# pqfb100-breakout.net
KiCad netlist of a schematic drawn in EAGLE
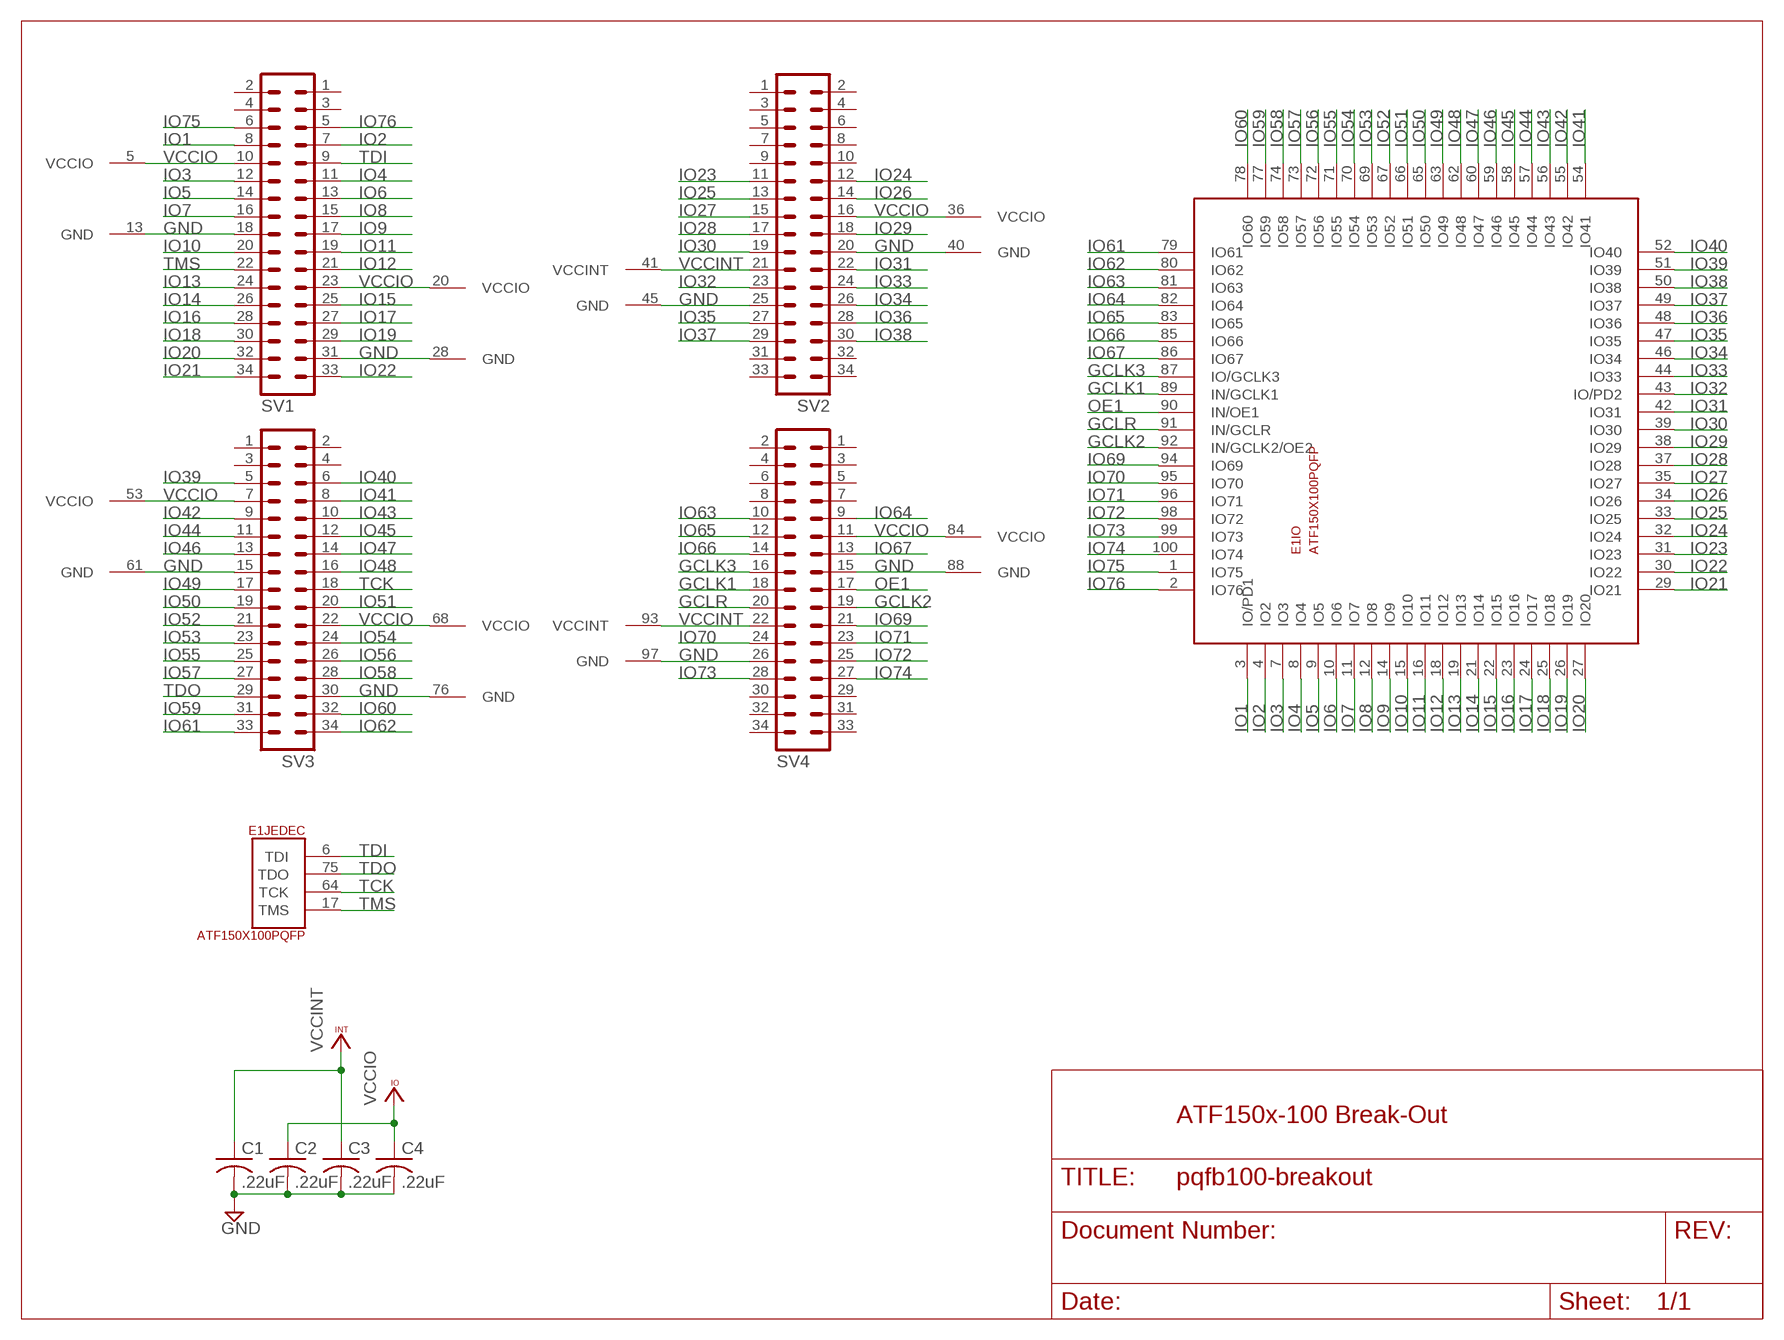
[diagram p0: schematic, sheet 1]

(export (version "E")
  (design (tool "Eeschema 10.0.6"))
  (components
    (comp (ref "C1")
      (value ".22uF")
      (footprint "eagle-import:C063-025X075")
      (libsource (lib "eagle-import") (part "C-US"))
    )
    (comp (ref "C2")
      (value ".22uF")
      (footprint "eagle-import:C063-025X075")
      (libsource (lib "eagle-import") (part "C-US"))
    )
    (comp (ref "C3")
      (value ".22uF")
      (footprint "eagle-import:C063-025X075")
      (libsource (lib "eagle-import") (part "C-US"))
    )
    (comp (ref "C4")
      (value ".22uF")
      (footprint "eagle-import:C063-025X075")
      (libsource (lib "eagle-import") (part "C-US"))
    )
    (comp (ref "E1")
      (value "ATF150X100PQFP")
      (footprint "eagle-import:PQFP-100")
      (libsource (lib "eagle-import") (part "ATF150X100PQFP"))
    )
    (comp (ref "SV1")
      (value "MA17-2")
      (footprint "eagle-import:MA17-2")
      (libsource (lib "eagle-import") (part "MA17-2"))
    )
    (comp (ref "SV2")
      (value "MA17-2")
      (footprint "eagle-import:MA17-2")
      (libsource (lib "eagle-import") (part "MA17-2"))
    )
    (comp (ref "SV3")
      (value "MA17-2")
      (footprint "eagle-import:MA17-2")
      (libsource (lib "eagle-import") (part "MA17-2"))
    )
    (comp (ref "SV4")
      (value "MA17-2")
      (footprint "eagle-import:MA17-2")
      (libsource (lib "eagle-import") (part "MA17-2"))
    )
  )
  (nets
    (net (code "1") (name "/GCLK1") (class "Default")
      (node (ref "E1") (pin "89") (pinfunction "IN/GCLK1_89") (pintype "input"))
      (node (ref "SV4") (pin "18") (pinfunction "18_18") (pintype "passive"))
    )
    (net (code "2") (name "/GCLK2") (class "Default")
      (node (ref "E1") (pin "92") (pinfunction "IN/GCLK2/OE2_92") (pintype "input"))
      (node (ref "SV4") (pin "19") (pinfunction "19_19") (pintype "passive"))
    )
    (net (code "3") (name "/GCLK3") (class "Default")
      (node (ref "E1") (pin "87") (pinfunction "IO/GCLK3_87") (pintype "bidirectional"))
      (node (ref "SV4") (pin "16") (pinfunction "16_16") (pintype "passive"))
    )
    (net (code "4") (name "/GCLR") (class "Default")
      (node (ref "E1") (pin "91") (pinfunction "IN/GCLR_91") (pintype "input"))
      (node (ref "SV4") (pin "20") (pinfunction "20_20") (pintype "passive"))
    )
    (net (code "5") (name "/IO1") (class "Default")
      (node (ref "E1") (pin "3") (pinfunction "IO/PD1_3") (pintype "bidirectional"))
      (node (ref "SV1") (pin "8") (pinfunction "8_8") (pintype "passive"))
    )
    (net (code "6") (name "/IO2") (class "Default")
      (node (ref "E1") (pin "4") (pinfunction "IO2_4") (pintype "bidirectional"))
      (node (ref "SV1") (pin "7") (pinfunction "7_7") (pintype "passive"))
    )
    (net (code "7") (name "/IO3") (class "Default")
      (node (ref "E1") (pin "7") (pinfunction "IO3_7") (pintype "bidirectional"))
      (node (ref "SV1") (pin "12") (pinfunction "12_12") (pintype "passive"))
    )
    (net (code "8") (name "/IO4") (class "Default")
      (node (ref "E1") (pin "8") (pinfunction "IO4_8") (pintype "bidirectional"))
      (node (ref "SV1") (pin "11") (pinfunction "11_11") (pintype "passive"))
    )
    (net (code "9") (name "/IO5") (class "Default")
      (node (ref "E1") (pin "9") (pinfunction "IO5_9") (pintype "bidirectional"))
      (node (ref "SV1") (pin "14") (pinfunction "14_14") (pintype "passive"))
    )
    (net (code "10") (name "/IO6") (class "Default")
      (node (ref "E1") (pin "10") (pinfunction "IO6_10") (pintype "bidirectional"))
      (node (ref "SV1") (pin "13") (pinfunction "13_13") (pintype "passive"))
    )
    (net (code "11") (name "/IO7") (class "Default")
      (node (ref "E1") (pin "11") (pinfunction "IO7_11") (pintype "bidirectional"))
      (node (ref "SV1") (pin "16") (pinfunction "16_16") (pintype "passive"))
    )
    (net (code "12") (name "/IO8") (class "Default")
      (node (ref "E1") (pin "12") (pinfunction "IO8_12") (pintype "bidirectional"))
      (node (ref "SV1") (pin "15") (pinfunction "15_15") (pintype "passive"))
    )
    (net (code "13") (name "/IO9") (class "Default")
      (node (ref "E1") (pin "14") (pinfunction "IO9_14") (pintype "bidirectional"))
      (node (ref "SV1") (pin "17") (pinfunction "17_17") (pintype "passive"))
    )
    (net (code "14") (name "/IO10") (class "Default")
      (node (ref "E1") (pin "15") (pinfunction "IO10_15") (pintype "bidirectional"))
      (node (ref "SV1") (pin "20") (pinfunction "20_20") (pintype "passive"))
    )
    (net (code "15") (name "/IO11") (class "Default")
      (node (ref "E1") (pin "16") (pinfunction "IO11_16") (pintype "bidirectional"))
      (node (ref "SV1") (pin "19") (pinfunction "19_19") (pintype "passive"))
    )
    (net (code "16") (name "/IO12") (class "Default")
      (node (ref "E1") (pin "18") (pinfunction "IO12_18") (pintype "bidirectional"))
      (node (ref "SV1") (pin "21") (pinfunction "21_21") (pintype "passive"))
    )
    (net (code "17") (name "/IO13") (class "Default")
      (node (ref "E1") (pin "19") (pinfunction "IO13_19") (pintype "bidirectional"))
      (node (ref "SV1") (pin "24") (pinfunction "24_24") (pintype "passive"))
    )
    (net (code "18") (name "/IO14") (class "Default")
      (node (ref "E1") (pin "21") (pinfunction "IO14_21") (pintype "bidirectional"))
      (node (ref "SV1") (pin "26") (pinfunction "26_26") (pintype "passive"))
    )
    (net (code "19") (name "/IO15") (class "Default")
      (node (ref "E1") (pin "22") (pinfunction "IO15_22") (pintype "bidirectional"))
      (node (ref "SV1") (pin "25") (pinfunction "25_25") (pintype "passive"))
    )
    (net (code "20") (name "/IO16") (class "Default")
      (node (ref "E1") (pin "23") (pinfunction "IO16_23") (pintype "bidirectional"))
      (node (ref "SV1") (pin "28") (pinfunction "28_28") (pintype "passive"))
    )
    (net (code "21") (name "/IO17") (class "Default")
      (node (ref "E1") (pin "24") (pinfunction "IO17_24") (pintype "bidirectional"))
      (node (ref "SV1") (pin "27") (pinfunction "27_27") (pintype "passive"))
    )
    (net (code "22") (name "/IO18") (class "Default")
      (node (ref "E1") (pin "25") (pinfunction "IO18_25") (pintype "bidirectional"))
      (node (ref "SV1") (pin "30") (pinfunction "30_30") (pintype "passive"))
    )
    (net (code "23") (name "/IO19") (class "Default")
      (node (ref "E1") (pin "26") (pinfunction "IO19_26") (pintype "bidirectional"))
      (node (ref "SV1") (pin "29") (pinfunction "29_29") (pintype "passive"))
    )
    (net (code "24") (name "/IO20") (class "Default")
      (node (ref "E1") (pin "27") (pinfunction "IO20_27") (pintype "bidirectional"))
      (node (ref "SV1") (pin "32") (pinfunction "32_32") (pintype "passive"))
    )
    (net (code "25") (name "/IO21") (class "Default")
      (node (ref "E1") (pin "29") (pinfunction "IO21_29") (pintype "bidirectional"))
      (node (ref "SV1") (pin "34") (pinfunction "34_34") (pintype "passive"))
    )
    (net (code "26") (name "/IO22") (class "Default")
      (node (ref "E1") (pin "30") (pinfunction "IO22_30") (pintype "bidirectional"))
      (node (ref "SV1") (pin "33") (pinfunction "33_33") (pintype "passive"))
    )
    (net (code "27") (name "/IO23") (class "Default")
      (node (ref "E1") (pin "31") (pinfunction "IO23_31") (pintype "bidirectional"))
      (node (ref "SV2") (pin "11") (pinfunction "11_11") (pintype "passive"))
    )
    (net (code "28") (name "/IO24") (class "Default")
      (node (ref "E1") (pin "32") (pinfunction "IO24_32") (pintype "bidirectional"))
      (node (ref "SV2") (pin "12") (pinfunction "12_12") (pintype "passive"))
    )
    (net (code "29") (name "/IO25") (class "Default")
      (node (ref "E1") (pin "33") (pinfunction "IO25_33") (pintype "bidirectional"))
      (node (ref "SV2") (pin "13") (pinfunction "13_13") (pintype "passive"))
    )
    (net (code "30") (name "/IO26") (class "Default")
      (node (ref "E1") (pin "34") (pinfunction "IO26_34") (pintype "bidirectional"))
      (node (ref "SV2") (pin "14") (pinfunction "14_14") (pintype "passive"))
    )
    (net (code "31") (name "/IO27") (class "Default")
      (node (ref "E1") (pin "35") (pinfunction "IO27_35") (pintype "bidirectional"))
      (node (ref "SV2") (pin "15") (pinfunction "15_15") (pintype "passive"))
    )
    (net (code "32") (name "/IO28") (class "Default")
      (node (ref "E1") (pin "37") (pinfunction "IO28_37") (pintype "bidirectional"))
      (node (ref "SV2") (pin "17") (pinfunction "17_17") (pintype "passive"))
    )
    (net (code "33") (name "/IO29") (class "Default")
      (node (ref "E1") (pin "38") (pinfunction "IO29_38") (pintype "bidirectional"))
      (node (ref "SV2") (pin "18") (pinfunction "18_18") (pintype "passive"))
    )
    (net (code "34") (name "/IO30") (class "Default")
      (node (ref "E1") (pin "39") (pinfunction "IO30_39") (pintype "bidirectional"))
      (node (ref "SV2") (pin "19") (pinfunction "19_19") (pintype "passive"))
    )
    (net (code "35") (name "/IO31") (class "Default")
      (node (ref "E1") (pin "42") (pinfunction "IO31_42") (pintype "bidirectional"))
      (node (ref "SV2") (pin "22") (pinfunction "22_22") (pintype "passive"))
    )
    (net (code "36") (name "/IO32") (class "Default")
      (node (ref "E1") (pin "43") (pinfunction "IO/PD2_43") (pintype "bidirectional"))
      (node (ref "SV2") (pin "23") (pinfunction "23_23") (pintype "passive"))
    )
    (net (code "37") (name "/IO33") (class "Default")
      (node (ref "E1") (pin "44") (pinfunction "IO33_44") (pintype "bidirectional"))
      (node (ref "SV2") (pin "24") (pinfunction "24_24") (pintype "passive"))
    )
    (net (code "38") (name "/IO34") (class "Default")
      (node (ref "E1") (pin "46") (pinfunction "IO34_46") (pintype "bidirectional"))
      (node (ref "SV2") (pin "26") (pinfunction "26_26") (pintype "passive"))
    )
    (net (code "39") (name "/IO35") (class "Default")
      (node (ref "E1") (pin "47") (pinfunction "IO35_47") (pintype "bidirectional"))
      (node (ref "SV2") (pin "27") (pinfunction "27_27") (pintype "passive"))
    )
    (net (code "40") (name "/IO36") (class "Default")
      (node (ref "E1") (pin "48") (pinfunction "IO36_48") (pintype "bidirectional"))
      (node (ref "SV2") (pin "28") (pinfunction "28_28") (pintype "passive"))
    )
    (net (code "41") (name "/IO37") (class "Default")
      (node (ref "E1") (pin "49") (pinfunction "IO37_49") (pintype "bidirectional"))
      (node (ref "SV2") (pin "29") (pinfunction "29_29") (pintype "passive"))
    )
    (net (code "42") (name "/IO38") (class "Default")
      (node (ref "E1") (pin "50") (pinfunction "IO38_50") (pintype "bidirectional"))
      (node (ref "SV2") (pin "30") (pinfunction "30_30") (pintype "passive"))
    )
    (net (code "43") (name "/IO39") (class "Default")
      (node (ref "E1") (pin "51") (pinfunction "IO39_51") (pintype "bidirectional"))
      (node (ref "SV3") (pin "5") (pinfunction "5_5") (pintype "passive"))
    )
    (net (code "44") (name "/IO40") (class "Default")
      (node (ref "E1") (pin "52") (pinfunction "IO40_52") (pintype "bidirectional"))
      (node (ref "SV3") (pin "6") (pinfunction "6_6") (pintype "passive"))
    )
    (net (code "45") (name "/IO41") (class "Default")
      (node (ref "E1") (pin "54") (pinfunction "IO41_54") (pintype "bidirectional"))
      (node (ref "SV3") (pin "8") (pinfunction "8_8") (pintype "passive"))
    )
    (net (code "46") (name "/IO42") (class "Default")
      (node (ref "E1") (pin "55") (pinfunction "IO42_55") (pintype "bidirectional"))
      (node (ref "SV3") (pin "9") (pinfunction "9_9") (pintype "passive"))
    )
    (net (code "47") (name "/IO43") (class "Default")
      (node (ref "E1") (pin "56") (pinfunction "IO43_56") (pintype "bidirectional"))
      (node (ref "SV3") (pin "10") (pinfunction "10_10") (pintype "passive"))
    )
    (net (code "48") (name "/IO44") (class "Default")
      (node (ref "E1") (pin "57") (pinfunction "IO44_57") (pintype "bidirectional"))
      (node (ref "SV3") (pin "11") (pinfunction "11_11") (pintype "passive"))
    )
    (net (code "49") (name "/IO45") (class "Default")
      (node (ref "E1") (pin "58") (pinfunction "IO45_58") (pintype "bidirectional"))
      (node (ref "SV3") (pin "12") (pinfunction "12_12") (pintype "passive"))
    )
    (net (code "50") (name "/IO46") (class "Default")
      (node (ref "E1") (pin "59") (pinfunction "IO46_59") (pintype "bidirectional"))
      (node (ref "SV3") (pin "13") (pinfunction "13_13") (pintype "passive"))
    )
    (net (code "51") (name "/IO47") (class "Default")
      (node (ref "E1") (pin "60") (pinfunction "IO47_60") (pintype "bidirectional"))
      (node (ref "SV3") (pin "14") (pinfunction "14_14") (pintype "passive"))
    )
    (net (code "52") (name "/IO48") (class "Default")
      (node (ref "E1") (pin "62") (pinfunction "IO48_62") (pintype "bidirectional"))
      (node (ref "SV3") (pin "16") (pinfunction "16_16") (pintype "passive"))
    )
    (net (code "53") (name "/IO49") (class "Default")
      (node (ref "E1") (pin "63") (pinfunction "IO49_63") (pintype "bidirectional"))
      (node (ref "SV3") (pin "17") (pinfunction "17_17") (pintype "passive"))
    )
    (net (code "54") (name "/IO50") (class "Default")
      (node (ref "E1") (pin "65") (pinfunction "IO50_65") (pintype "bidirectional"))
      (node (ref "SV3") (pin "19") (pinfunction "19_19") (pintype "passive"))
    )
    (net (code "55") (name "/IO51") (class "Default")
      (node (ref "E1") (pin "66") (pinfunction "IO51_66") (pintype "bidirectional"))
      (node (ref "SV3") (pin "20") (pinfunction "20_20") (pintype "passive"))
    )
    (net (code "56") (name "/IO52") (class "Default")
      (node (ref "E1") (pin "67") (pinfunction "IO52_67") (pintype "bidirectional"))
      (node (ref "SV3") (pin "21") (pinfunction "21_21") (pintype "passive"))
    )
    (net (code "57") (name "/IO53") (class "Default")
      (node (ref "E1") (pin "69") (pinfunction "IO53_69") (pintype "bidirectional"))
      (node (ref "SV3") (pin "23") (pinfunction "23_23") (pintype "passive"))
    )
    (net (code "58") (name "/IO54") (class "Default")
      (node (ref "E1") (pin "70") (pinfunction "IO54_70") (pintype "bidirectional"))
      (node (ref "SV3") (pin "24") (pinfunction "24_24") (pintype "passive"))
    )
    (net (code "59") (name "/IO55") (class "Default")
      (node (ref "E1") (pin "71") (pinfunction "IO55_71") (pintype "bidirectional"))
      (node (ref "SV3") (pin "25") (pinfunction "25_25") (pintype "passive"))
    )
    (net (code "60") (name "/IO56") (class "Default")
      (node (ref "E1") (pin "72") (pinfunction "IO56_72") (pintype "bidirectional"))
      (node (ref "SV3") (pin "26") (pinfunction "26_26") (pintype "passive"))
    )
    (net (code "61") (name "/IO57") (class "Default")
      (node (ref "E1") (pin "73") (pinfunction "IO57_73") (pintype "bidirectional"))
      (node (ref "SV3") (pin "27") (pinfunction "27_27") (pintype "passive"))
    )
    (net (code "62") (name "/IO58") (class "Default")
      (node (ref "E1") (pin "74") (pinfunction "IO58_74") (pintype "bidirectional"))
      (node (ref "SV3") (pin "28") (pinfunction "28_28") (pintype "passive"))
    )
    (net (code "63") (name "/IO59") (class "Default")
      (node (ref "E1") (pin "77") (pinfunction "IO59_77") (pintype "bidirectional"))
      (node (ref "SV3") (pin "31") (pinfunction "31_31") (pintype "passive"))
    )
    (net (code "64") (name "/IO60") (class "Default")
      (node (ref "E1") (pin "78") (pinfunction "IO60_78") (pintype "bidirectional"))
      (node (ref "SV3") (pin "32") (pinfunction "32_32") (pintype "passive"))
    )
    (net (code "65") (name "/IO61") (class "Default")
      (node (ref "E1") (pin "79") (pinfunction "IO61_79") (pintype "bidirectional"))
      (node (ref "SV3") (pin "33") (pinfunction "33_33") (pintype "passive"))
    )
    (net (code "66") (name "/IO62") (class "Default")
      (node (ref "E1") (pin "80") (pinfunction "IO62_80") (pintype "bidirectional"))
      (node (ref "SV3") (pin "34") (pinfunction "34_34") (pintype "passive"))
    )
    (net (code "67") (name "/IO63") (class "Default")
      (node (ref "E1") (pin "81") (pinfunction "IO63_81") (pintype "bidirectional"))
      (node (ref "SV4") (pin "10") (pinfunction "10_10") (pintype "passive"))
    )
    (net (code "68") (name "/IO64") (class "Default")
      (node (ref "E1") (pin "82") (pinfunction "IO64_82") (pintype "bidirectional"))
      (node (ref "SV4") (pin "9") (pinfunction "9_9") (pintype "passive"))
    )
    (net (code "69") (name "/IO65") (class "Default")
      (node (ref "E1") (pin "83") (pinfunction "IO65_83") (pintype "bidirectional"))
      (node (ref "SV4") (pin "12") (pinfunction "12_12") (pintype "passive"))
    )
    (net (code "70") (name "/IO66") (class "Default")
      (node (ref "E1") (pin "85") (pinfunction "IO66_85") (pintype "bidirectional"))
      (node (ref "SV4") (pin "14") (pinfunction "14_14") (pintype "passive"))
    )
    (net (code "71") (name "/IO67") (class "Default")
      (node (ref "E1") (pin "86") (pinfunction "IO67_86") (pintype "bidirectional"))
      (node (ref "SV4") (pin "13") (pinfunction "13_13") (pintype "passive"))
    )
    (net (code "72") (name "/IO69") (class "Default")
      (node (ref "E1") (pin "94") (pinfunction "IO69_94") (pintype "bidirectional"))
      (node (ref "SV4") (pin "21") (pinfunction "21_21") (pintype "passive"))
    )
    (net (code "73") (name "/IO70") (class "Default")
      (node (ref "E1") (pin "95") (pinfunction "IO70_95") (pintype "bidirectional"))
      (node (ref "SV4") (pin "24") (pinfunction "24_24") (pintype "passive"))
    )
    (net (code "74") (name "/IO71") (class "Default")
      (node (ref "E1") (pin "96") (pinfunction "IO71_96") (pintype "bidirectional"))
      (node (ref "SV4") (pin "23") (pinfunction "23_23") (pintype "passive"))
    )
    (net (code "75") (name "/IO72") (class "Default")
      (node (ref "E1") (pin "98") (pinfunction "IO72_98") (pintype "bidirectional"))
      (node (ref "SV4") (pin "25") (pinfunction "25_25") (pintype "passive"))
    )
    (net (code "76") (name "/IO73") (class "Default")
      (node (ref "E1") (pin "99") (pinfunction "IO73_99") (pintype "bidirectional"))
      (node (ref "SV4") (pin "28") (pinfunction "28_28") (pintype "passive"))
    )
    (net (code "77") (name "/IO74") (class "Default")
      (node (ref "E1") (pin "100") (pinfunction "IO74_100") (pintype "bidirectional"))
      (node (ref "SV4") (pin "27") (pinfunction "27_27") (pintype "passive"))
    )
    (net (code "78") (name "/IO75") (class "Default")
      (node (ref "E1") (pin "1") (pinfunction "IO75_1") (pintype "bidirectional"))
      (node (ref "SV1") (pin "6") (pinfunction "6_6") (pintype "passive"))
    )
    (net (code "79") (name "/IO76") (class "Default")
      (node (ref "E1") (pin "2") (pinfunction "IO76_2") (pintype "bidirectional"))
      (node (ref "SV1") (pin "5") (pinfunction "5_5") (pintype "passive"))
    )
    (net (code "80") (name "/OE1") (class "Default")
      (node (ref "E1") (pin "90") (pinfunction "IN/OE1_90") (pintype "input"))
      (node (ref "SV4") (pin "17") (pinfunction "17_17") (pintype "passive"))
    )
    (net (code "81") (name "/TCK") (class "Default")
      (node (ref "E1") (pin "64") (pinfunction "TCK_64") (pintype "bidirectional"))
      (node (ref "SV3") (pin "18") (pinfunction "18_18") (pintype "passive"))
    )
    (net (code "82") (name "/TDI") (class "Default")
      (node (ref "E1") (pin "6") (pinfunction "TDI_6") (pintype "bidirectional"))
      (node (ref "SV1") (pin "9") (pinfunction "9_9") (pintype "passive"))
    )
    (net (code "83") (name "/TDO") (class "Default")
      (node (ref "E1") (pin "75") (pinfunction "TDO_75") (pintype "bidirectional"))
      (node (ref "SV3") (pin "29") (pinfunction "29_29") (pintype "passive"))
    )
    (net (code "84") (name "/TMS") (class "Default")
      (node (ref "E1") (pin "17") (pinfunction "TMS_17") (pintype "bidirectional"))
      (node (ref "SV1") (pin "22") (pinfunction "22_22") (pintype "passive"))
    )
    (net (code "85") (name "GND") (class "Default")
      (node (ref "C1") (pin "2") (pinfunction "2_2") (pintype "passive"))
      (node (ref "C2") (pin "2") (pinfunction "2_2") (pintype "passive"))
      (node (ref "C3") (pin "2") (pinfunction "2_2") (pintype "passive"))
      (node (ref "C4") (pin "2") (pinfunction "2_2") (pintype "passive"))
      (node (ref "E1") (pin "13") (pinfunction "GND_13") (pintype "power_in"))
      (node (ref "E1") (pin "28") (pinfunction "GND_28") (pintype "power_in"))
      (node (ref "E1") (pin "40") (pinfunction "GND_40") (pintype "power_in"))
      (node (ref "E1") (pin "45") (pinfunction "GND_45") (pintype "power_in"))
      (node (ref "E1") (pin "61") (pinfunction "GND_61") (pintype "power_in"))
      (node (ref "E1") (pin "76") (pinfunction "GND_76") (pintype "power_in"))
      (node (ref "E1") (pin "88") (pinfunction "GND_88") (pintype "power_in"))
      (node (ref "E1") (pin "97") (pinfunction "GND_97") (pintype "power_in"))
      (node (ref "SV1") (pin "18") (pinfunction "18_18") (pintype "passive"))
      (node (ref "SV1") (pin "31") (pinfunction "31_31") (pintype "passive"))
      (node (ref "SV2") (pin "20") (pinfunction "20_20") (pintype "passive"))
      (node (ref "SV2") (pin "25") (pinfunction "25_25") (pintype "passive"))
      (node (ref "SV3") (pin "15") (pinfunction "15_15") (pintype "passive"))
      (node (ref "SV3") (pin "30") (pinfunction "30_30") (pintype "passive"))
      (node (ref "SV4") (pin "15") (pinfunction "15_15") (pintype "passive"))
      (node (ref "SV4") (pin "26") (pinfunction "26_26") (pintype "passive"))
    )
    (net (code "86") (name "VCCINT") (class "Default")
      (node (ref "C1") (pin "1") (pinfunction "1_1") (pintype "passive"))
      (node (ref "C3") (pin "1") (pinfunction "1_1") (pintype "passive"))
      (node (ref "E1") (pin "41") (pinfunction "VCCINT_41") (pintype "power_in"))
      (node (ref "E1") (pin "93") (pinfunction "VCCINT_93") (pintype "power_in"))
      (node (ref "SV2") (pin "21") (pinfunction "21_21") (pintype "passive"))
      (node (ref "SV4") (pin "22") (pinfunction "22_22") (pintype "passive"))
    )
    (net (code "87") (name "VCCIO") (class "Default")
      (node (ref "C2") (pin "1") (pinfunction "1_1") (pintype "passive"))
      (node (ref "C4") (pin "1") (pinfunction "1_1") (pintype "passive"))
      (node (ref "E1") (pin "20") (pinfunction "VCCIO_20") (pintype "power_in"))
      (node (ref "E1") (pin "36") (pinfunction "VCCIO_36") (pintype "power_in"))
      (node (ref "E1") (pin "5") (pinfunction "VCCIO_5") (pintype "power_in"))
      (node (ref "E1") (pin "53") (pinfunction "VCCIO_53") (pintype "power_in"))
      (node (ref "E1") (pin "68") (pinfunction "VCCIO_68") (pintype "power_in"))
      (node (ref "E1") (pin "84") (pinfunction "VCCIO_84") (pintype "power_in"))
      (node (ref "SV1") (pin "10") (pinfunction "10_10") (pintype "passive"))
      (node (ref "SV1") (pin "23") (pinfunction "23_23") (pintype "passive"))
      (node (ref "SV2") (pin "16") (pinfunction "16_16") (pintype "passive"))
      (node (ref "SV3") (pin "22") (pinfunction "22_22") (pintype "passive"))
      (node (ref "SV3") (pin "7") (pinfunction "7_7") (pintype "passive"))
      (node (ref "SV4") (pin "11") (pinfunction "11_11") (pintype "passive"))
    )
    (net (code "88") (name "unconnected-(SV1-Pad1)") (class "Default")
      (node (ref "SV1") (pin "1") (pinfunction "1_1") (pintype "passive"))
    )
    (net (code "89") (name "unconnected-(SV1-Pad2)") (class "Default")
      (node (ref "SV1") (pin "2") (pinfunction "2_2") (pintype "passive"))
    )
    (net (code "90") (name "unconnected-(SV1-Pad3)") (class "Default")
      (node (ref "SV1") (pin "3") (pinfunction "3_3") (pintype "passive"))
    )
    (net (code "91") (name "unconnected-(SV1-Pad4)") (class "Default")
      (node (ref "SV1") (pin "4") (pinfunction "4_4") (pintype "passive"))
    )
    (net (code "92") (name "unconnected-(SV2-Pad1)") (class "Default")
      (node (ref "SV2") (pin "1") (pinfunction "1_1") (pintype "passive"))
    )
    (net (code "93") (name "unconnected-(SV2-Pad2)") (class "Default")
      (node (ref "SV2") (pin "2") (pinfunction "2_2") (pintype "passive"))
    )
    (net (code "94") (name "unconnected-(SV2-Pad3)") (class "Default")
      (node (ref "SV2") (pin "3") (pinfunction "3_3") (pintype "passive"))
    )
    (net (code "95") (name "unconnected-(SV2-Pad4)") (class "Default")
      (node (ref "SV2") (pin "4") (pinfunction "4_4") (pintype "passive"))
    )
    (net (code "96") (name "unconnected-(SV2-Pad5)") (class "Default")
      (node (ref "SV2") (pin "5") (pinfunction "5_5") (pintype "passive"))
    )
    (net (code "97") (name "unconnected-(SV2-Pad6)") (class "Default")
      (node (ref "SV2") (pin "6") (pinfunction "6_6") (pintype "passive"))
    )
    (net (code "98") (name "unconnected-(SV2-Pad7)") (class "Default")
      (node (ref "SV2") (pin "7") (pinfunction "7_7") (pintype "passive"))
    )
    (net (code "99") (name "unconnected-(SV2-Pad8)") (class "Default")
      (node (ref "SV2") (pin "8") (pinfunction "8_8") (pintype "passive"))
    )
    (net (code "100") (name "unconnected-(SV2-Pad9)") (class "Default")
      (node (ref "SV2") (pin "9") (pinfunction "9_9") (pintype "passive"))
    )
    (net (code "101") (name "unconnected-(SV2-Pad10)") (class "Default")
      (node (ref "SV2") (pin "10") (pinfunction "10_10") (pintype "passive"))
    )
    (net (code "102") (name "unconnected-(SV2-Pad31)") (class "Default")
      (node (ref "SV2") (pin "31") (pinfunction "31_31") (pintype "passive"))
    )
    (net (code "103") (name "unconnected-(SV2-Pad32)") (class "Default")
      (node (ref "SV2") (pin "32") (pinfunction "32_32") (pintype "passive"))
    )
    (net (code "104") (name "unconnected-(SV2-Pad33)") (class "Default")
      (node (ref "SV2") (pin "33") (pinfunction "33_33") (pintype "passive"))
    )
    (net (code "105") (name "unconnected-(SV2-Pad34)") (class "Default")
      (node (ref "SV2") (pin "34") (pinfunction "34_34") (pintype "passive"))
    )
    (net (code "106") (name "unconnected-(SV3-Pad1)") (class "Default")
      (node (ref "SV3") (pin "1") (pinfunction "1_1") (pintype "passive"))
    )
    (net (code "107") (name "unconnected-(SV3-Pad2)") (class "Default")
      (node (ref "SV3") (pin "2") (pinfunction "2_2") (pintype "passive"))
    )
    (net (code "108") (name "unconnected-(SV3-Pad3)") (class "Default")
      (node (ref "SV3") (pin "3") (pinfunction "3_3") (pintype "passive"))
    )
    (net (code "109") (name "unconnected-(SV3-Pad4)") (class "Default")
      (node (ref "SV3") (pin "4") (pinfunction "4_4") (pintype "passive"))
    )
    (net (code "110") (name "unconnected-(SV4-Pad1)") (class "Default")
      (node (ref "SV4") (pin "1") (pinfunction "1_1") (pintype "passive"))
    )
    (net (code "111") (name "unconnected-(SV4-Pad2)") (class "Default")
      (node (ref "SV4") (pin "2") (pinfunction "2_2") (pintype "passive"))
    )
    (net (code "112") (name "unconnected-(SV4-Pad3)") (class "Default")
      (node (ref "SV4") (pin "3") (pinfunction "3_3") (pintype "passive"))
    )
    (net (code "113") (name "unconnected-(SV4-Pad4)") (class "Default")
      (node (ref "SV4") (pin "4") (pinfunction "4_4") (pintype "passive"))
    )
    (net (code "114") (name "unconnected-(SV4-Pad5)") (class "Default")
      (node (ref "SV4") (pin "5") (pinfunction "5_5") (pintype "passive"))
    )
    (net (code "115") (name "unconnected-(SV4-Pad6)") (class "Default")
      (node (ref "SV4") (pin "6") (pinfunction "6_6") (pintype "passive"))
    )
    (net (code "116") (name "unconnected-(SV4-Pad7)") (class "Default")
      (node (ref "SV4") (pin "7") (pinfunction "7_7") (pintype "passive"))
    )
    (net (code "117") (name "unconnected-(SV4-Pad8)") (class "Default")
      (node (ref "SV4") (pin "8") (pinfunction "8_8") (pintype "passive"))
    )
    (net (code "118") (name "unconnected-(SV4-Pad29)") (class "Default")
      (node (ref "SV4") (pin "29") (pinfunction "29_29") (pintype "passive"))
    )
    (net (code "119") (name "unconnected-(SV4-Pad30)") (class "Default")
      (node (ref "SV4") (pin "30") (pinfunction "30_30") (pintype "passive"))
    )
    (net (code "120") (name "unconnected-(SV4-Pad31)") (class "Default")
      (node (ref "SV4") (pin "31") (pinfunction "31_31") (pintype "passive"))
    )
    (net (code "121") (name "unconnected-(SV4-Pad32)") (class "Default")
      (node (ref "SV4") (pin "32") (pinfunction "32_32") (pintype "passive"))
    )
    (net (code "122") (name "unconnected-(SV4-Pad33)") (class "Default")
      (node (ref "SV4") (pin "33") (pinfunction "33_33") (pintype "passive"))
    )
    (net (code "123") (name "unconnected-(SV4-Pad34)") (class "Default")
      (node (ref "SV4") (pin "34") (pinfunction "34_34") (pintype "passive"))
    )
  )
)
